# Solar_Panel.net
KiCad netlist of a schematic drawn in Altium Designer
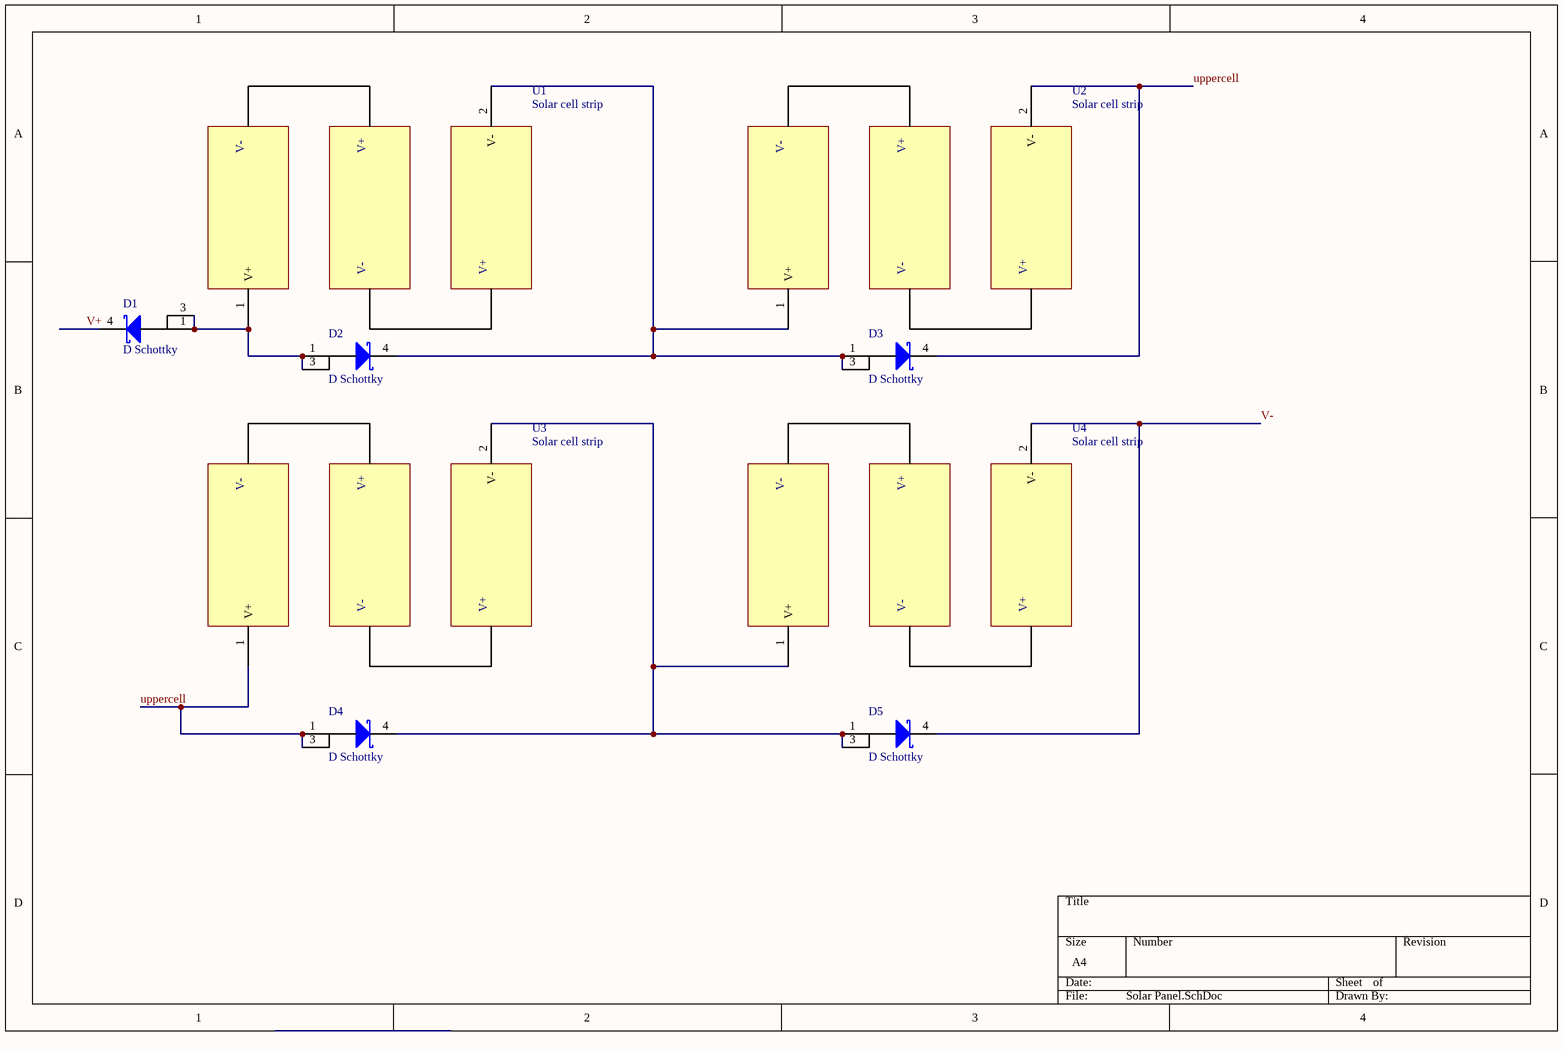
[diagram p0: Solar Panel.SchDoc]

(export (version "E")
  (design (tool "Eeschema 10.0.6"))
  (components
    (comp (ref "D1")
      (value "D Schottky")
      (footprint "DIODE, SCHOTTKY, DPAK")
      (description "Schottky Diode")
      (fields (field (name "PUBLISHER") "Altium Limited"))
      (libsource (lib "Solar cell strip") (part "D Schottky"))
    )
    (comp (ref "D2")
      (value "D Schottky")
      (footprint "DIODE, SCHOTTKY, DPAK")
      (description "Schottky Diode")
      (fields (field (name "PUBLISHER") "Altium Limited"))
      (libsource (lib "Solar cell strip") (part "D Schottky"))
    )
    (comp (ref "D3")
      (value "D Schottky")
      (footprint "DIODE, SCHOTTKY, DPAK")
      (description "Schottky Diode")
      (fields (field (name "PUBLISHER") "Altium Limited"))
      (libsource (lib "Solar cell strip") (part "D Schottky"))
    )
    (comp (ref "D4")
      (value "D Schottky")
      (footprint "DIODE, SCHOTTKY, DPAK")
      (description "Schottky Diode")
      (fields (field (name "PUBLISHER") "Altium Limited"))
      (libsource (lib "Solar cell strip") (part "D Schottky"))
    )
    (comp (ref "D5")
      (value "D Schottky")
      (footprint "DIODE, SCHOTTKY, DPAK")
      (description "Schottky Diode")
      (fields (field (name "PUBLISHER") "Altium Limited"))
      (libsource (lib "Solar cell strip") (part "D Schottky"))
    )
    (comp (ref "U1")
      (value "Solar cell strip")
      (footprint "SOLARCELLSTRIP")
      (libsource (lib "Solar cell strip") (part "Solar cell strip"))
    )
    (comp (ref "U2")
      (value "Solar cell strip")
      (footprint "SOLARCELLSTRIP")
      (libsource (lib "Solar cell strip") (part "Solar cell strip"))
    )
    (comp (ref "U3")
      (value "Solar cell strip")
      (footprint "SOLARCELLSTRIP")
      (libsource (lib "Solar cell strip") (part "Solar cell strip"))
    )
    (comp (ref "U4")
      (value "Solar cell strip")
      (footprint "SOLARCELLSTRIP")
      (libsource (lib "Solar cell strip") (part "Solar cell strip"))
    )
  )
  (nets
    (net (code "1") (name "/V+") (class "Default")
      (node (ref "D1") (pin "4") (pinfunction "K_4") (pintype "passive"))
    )
    (net (code "2") (name "/V-") (class "Default")
      (node (ref "D5") (pin "4") (pinfunction "K_4") (pintype "passive"))
      (node (ref "U4") (pin "2") (pinfunction "V-_2") (pintype "passive"))
    )
    (net (code "3") (name "/uppercell") (class "Default")
      (node (ref "D3") (pin "4") (pinfunction "K_4") (pintype "passive"))
      (node (ref "D4") (pin "1") (pinfunction "A_1") (pintype "passive"))
      (node (ref "D4") (pin "3") (pinfunction "A_3") (pintype "passive"))
      (node (ref "U2") (pin "2") (pinfunction "V-_2") (pintype "passive"))
      (node (ref "U3") (pin "1") (pinfunction "V+_1") (pintype "passive"))
    )
    (net (code "4") (name "Net-(D2-K)") (class "Default")
      (node (ref "D2") (pin "4") (pinfunction "K_4") (pintype "passive"))
      (node (ref "D3") (pin "1") (pinfunction "A_1") (pintype "passive"))
      (node (ref "D3") (pin "3") (pinfunction "A_3") (pintype "passive"))
      (node (ref "U1") (pin "2") (pinfunction "V-_2") (pintype "passive"))
      (node (ref "U2") (pin "1") (pinfunction "V+_1") (pintype "passive"))
    )
    (net (code "5") (name "Net-(D4-K)") (class "Default")
      (node (ref "D4") (pin "4") (pinfunction "K_4") (pintype "passive"))
      (node (ref "D5") (pin "1") (pinfunction "A_1") (pintype "passive"))
      (node (ref "D5") (pin "3") (pinfunction "A_3") (pintype "passive"))
      (node (ref "U3") (pin "2") (pinfunction "V-_2") (pintype "passive"))
      (node (ref "U4") (pin "1") (pinfunction "V+_1") (pintype "passive"))
    )
    (net (code "6") (name "Net-(U1-V+)") (class "Default")
      (node (ref "D1") (pin "1") (pinfunction "A_1") (pintype "passive"))
      (node (ref "D1") (pin "3") (pinfunction "A_3") (pintype "passive"))
      (node (ref "D2") (pin "1") (pinfunction "A_1") (pintype "passive"))
      (node (ref "D2") (pin "3") (pinfunction "A_3") (pintype "passive"))
      (node (ref "U1") (pin "1") (pinfunction "V+_1") (pintype "passive"))
    )
  )
)
